# Interfaz_RS232.net
KiCad netlist of a schematic drawn in Altium Designer
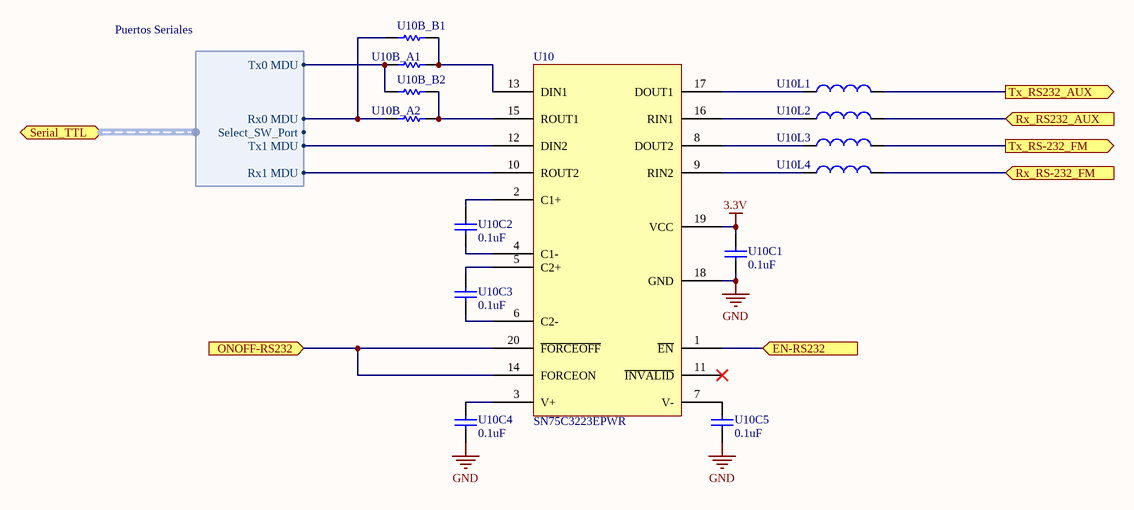
[diagram p0: Interfaz_RS232.SchDoc]

(export (version "E")
  (design (tool "Eeschema 10.0.6"))
  (components
    (comp (ref "U10")
      (value "SN75C3223EPWR")
      (footprint "TSSOP-20")
      (description "IC LINE DRVR/RCVR RS232 20-TSSOP")
      (fields (field (name "MANUFACTURER") "Texas Instruments"))
      (libsource (lib "LibreriaEstandar2") (part "SN75C3223EPWR"))
    )
    (comp (ref "U10B_A1")
      (value "~")
      (footprint "Bypass Bridge")
      (description "No Aplica")
      (libsource (lib "Miscellaneous Devices") (part "Res1"))
    )
    (comp (ref "U10B_A2")
      (value "~")
      (footprint "Bypass Bridge")
      (description "No Aplica")
      (libsource (lib "Miscellaneous Devices") (part "Res1"))
    )
    (comp (ref "U10B_B1")
      (value "~")
      (footprint "Bypass Bridge")
      (description "No Aplica")
      (libsource (lib "Miscellaneous Devices") (part "Res1"))
    )
    (comp (ref "U10B_B2")
      (value "~")
      (footprint "Bypass Bridge")
      (description "No Aplica")
      (libsource (lib "Miscellaneous Devices") (part "Res1"))
    )
    (comp (ref "U10C1")
      (value "0.1uF")
      (footprint "0603 - CAP")
      (description "CAP CERAMIC 0.1UF, 25V, X7R, 0603")
      (fields
        (field (name "MANUFACTURER PART NUMBER") "CGJ3E2X7R1E104K080AA")
        (field (name "MANUFACTURER") "TDK Corporation")
      )
      (libsource (lib "*") (part "Cap"))
    )
    (comp (ref "U10C2")
      (value "0.1uF")
      (footprint "0603 - CAP")
      (description "CAP CERAMIC 0.1UF, 25V, X7R, 0603")
      (fields
        (field (name "MANUFACTURER PART NUMBER") "CGJ3E2X7R1E104K080AA")
        (field (name "MANUFACTURER") "TDK Corporation")
      )
      (libsource (lib "*") (part "Cap"))
    )
    (comp (ref "U10C3")
      (value "0.1uF")
      (footprint "0603 - CAP")
      (description "CAP CERAMIC 0.1UF, 25V, X7R, 0603")
      (fields
        (field (name "MANUFACTURER PART NUMBER") "CGJ3E2X7R1E104K080AA")
        (field (name "MANUFACTURER") "TDK Corporation")
      )
      (libsource (lib "*") (part "Cap"))
    )
    (comp (ref "U10C4")
      (value "0.1uF")
      (footprint "0603 - CAP")
      (description "CAP CERAMIC 0.1UF, 25V, X7R, 0603")
      (fields
        (field (name "MANUFACTURER PART NUMBER") "CGJ3E2X7R1E104K080AA")
        (field (name "MANUFACTURER") "TDK Corporation")
      )
      (libsource (lib "*") (part "Cap"))
    )
    (comp (ref "U10C5")
      (value "0.1uF")
      (footprint "0603 - CAP")
      (description "CAP CERAMIC 0.1UF, 25V, X7R, 0603")
      (fields
        (field (name "MANUFACTURER PART NUMBER") "CGJ3E2X7R1E104K080AA")
        (field (name "MANUFACTURER") "TDK Corporation")
      )
      (libsource (lib "*") (part "Cap"))
    )
    (comp (ref "U10L1")
      (value "74279214")
      (footprint "1206-IND")
      (description "FERRITE BEAD 1000 OHM .20A 1206")
      (fields (field (name "MANUFACTURER") "Wurth Elektronik"))
      (libsource (lib "Miscellaneous Devices") (part "Inductor"))
    )
    (comp (ref "U10L2")
      (value "74279214")
      (footprint "1206-IND")
      (description "FERRITE BEAD 1000 OHM .20A 1206")
      (fields (field (name "MANUFACTURER") "Wurth Elektronik"))
      (libsource (lib "Miscellaneous Devices") (part "Inductor"))
    )
    (comp (ref "U10L3")
      (value "74279214")
      (footprint "1206-IND")
      (description "FERRITE BEAD 1000 OHM .20A 1206")
      (fields (field (name "MANUFACTURER") "Wurth Elektronik"))
      (libsource (lib "Miscellaneous Devices") (part "Inductor"))
    )
    (comp (ref "U10L4")
      (value "74279214")
      (footprint "1206-IND")
      (description "FERRITE BEAD 1000 OHM .20A 1206")
      (fields (field (name "MANUFACTURER") "Wurth Elektronik"))
      (libsource (lib "Miscellaneous Devices") (part "Inductor"))
    )
  )
  (nets
    (net (code "3") (name "/EN-RS232") (class "Default")
      (node (ref "U10") (pin "1") (pinfunction "~{EN}_1") (pintype "passive"))
    )
    (net (code "4") (name "/ONOFF-RS232") (class "Default")
      (node (ref "U10") (pin "14") (pinfunction "FORCEON_14") (pintype "passive"))
      (node (ref "U10") (pin "20") (pinfunction "~{FORCEOFF}_20") (pintype "passive"))
    )
    (net (code "5") (name "/Rx0 MDU") (class "Default")
      (node (ref "U10B_A2") (pin "1") (pinfunction "1_1") (pintype "passive"))
      (node (ref "U10B_B1") (pin "2") (pinfunction "2_2") (pintype "passive"))
    )
    (net (code "6") (name "/Rx1 MDU") (class "Default")
      (node (ref "U10") (pin "10") (pinfunction "ROUT2_10") (pintype "passive"))
    )
    (net (code "7") (name "/Rx_RS-232_FM") (class "Default")
      (node (ref "U10L4") (pin "2") (pinfunction "2_2") (pintype "passive"))
    )
    (net (code "8") (name "/Rx_RS232_AUX") (class "Default")
      (node (ref "U10L2") (pin "2") (pinfunction "2_2") (pintype "passive"))
    )
    (net (code "9") (name "/Tx0 MDU") (class "Default")
      (node (ref "U10B_A1") (pin "1") (pinfunction "1_1") (pintype "passive"))
      (node (ref "U10B_B2") (pin "2") (pinfunction "2_2") (pintype "passive"))
    )
    (net (code "10") (name "/Tx1 MDU") (class "Default")
      (node (ref "U10") (pin "12") (pinfunction "DIN2_12") (pintype "passive"))
    )
    (net (code "11") (name "/Tx_RS-232_FM") (class "Default")
      (node (ref "U10L3") (pin "2") (pinfunction "2_2") (pintype "passive"))
    )
    (net (code "12") (name "/Tx_RS232_AUX") (class "Default")
      (node (ref "U10L1") (pin "2") (pinfunction "2_2") (pintype "passive"))
    )
    (net (code "14") (name "3.3V") (class "Default")
      (node (ref "U10") (pin "19") (pinfunction "VCC_19") (pintype "passive"))
      (node (ref "U10C1") (pin "2") (pinfunction "2_2") (pintype "passive"))
    )
    (net (code "15") (name "GND") (class "Default")
      (node (ref "U10") (pin "18") (pinfunction "GND_18") (pintype "passive"))
      (node (ref "U10C1") (pin "1") (pinfunction "1_1") (pintype "passive"))
      (node (ref "U10C4") (pin "1") (pinfunction "1_1") (pintype "passive"))
      (node (ref "U10C5") (pin "1") (pinfunction "1_1") (pintype "passive"))
    )
    (net (code "16") (name "Net-(U10-C1+)") (class "Default")
      (node (ref "U10") (pin "2") (pinfunction "C1+_2") (pintype "passive"))
      (node (ref "U10C2") (pin "2") (pinfunction "2_2") (pintype "passive"))
    )
    (net (code "17") (name "Net-(U10-C1-)") (class "Default")
      (node (ref "U10") (pin "4") (pinfunction "C1-_4") (pintype "passive"))
      (node (ref "U10C2") (pin "1") (pinfunction "1_1") (pintype "passive"))
    )
    (net (code "18") (name "Net-(U10-C2+)") (class "Default")
      (node (ref "U10") (pin "5") (pinfunction "C2+_5") (pintype "passive"))
      (node (ref "U10C3") (pin "2") (pinfunction "2_2") (pintype "passive"))
    )
    (net (code "19") (name "Net-(U10-C2-)") (class "Default")
      (node (ref "U10") (pin "6") (pinfunction "C2-_6") (pintype "passive"))
      (node (ref "U10C3") (pin "1") (pinfunction "1_1") (pintype "passive"))
    )
    (net (code "20") (name "Net-(U10-DIN1)") (class "Default")
      (node (ref "U10") (pin "13") (pinfunction "DIN1_13") (pintype "passive"))
      (node (ref "U10B_A1") (pin "2") (pinfunction "2_2") (pintype "passive"))
      (node (ref "U10B_B1") (pin "1") (pinfunction "1_1") (pintype "passive"))
    )
    (net (code "21") (name "Net-(U10-DOUT1)") (class "Default")
      (node (ref "U10") (pin "17") (pinfunction "DOUT1_17") (pintype "passive"))
      (node (ref "U10L1") (pin "1") (pinfunction "1_1") (pintype "passive"))
    )
    (net (code "22") (name "Net-(U10-DOUT2)") (class "Default")
      (node (ref "U10") (pin "8") (pinfunction "DOUT2_8") (pintype "passive"))
      (node (ref "U10L3") (pin "1") (pinfunction "1_1") (pintype "passive"))
    )
    (net (code "23") (name "Net-(U10-RIN1)") (class "Default")
      (node (ref "U10") (pin "16") (pinfunction "RIN1_16") (pintype "passive"))
      (node (ref "U10L2") (pin "1") (pinfunction "1_1") (pintype "passive"))
    )
    (net (code "24") (name "Net-(U10-RIN2)") (class "Default")
      (node (ref "U10") (pin "9") (pinfunction "RIN2_9") (pintype "passive"))
      (node (ref "U10L4") (pin "1") (pinfunction "1_1") (pintype "passive"))
    )
    (net (code "25") (name "Net-(U10-ROUT1)") (class "Default")
      (node (ref "U10") (pin "15") (pinfunction "ROUT1_15") (pintype "passive"))
      (node (ref "U10B_A2") (pin "2") (pinfunction "2_2") (pintype "passive"))
      (node (ref "U10B_B2") (pin "1") (pinfunction "1_1") (pintype "passive"))
    )
    (net (code "26") (name "Net-(U10-V+)") (class "Default")
      (node (ref "U10") (pin "3") (pinfunction "V+_3") (pintype "passive"))
      (node (ref "U10C4") (pin "2") (pinfunction "2_2") (pintype "passive"))
    )
    (net (code "27") (name "Net-(U10-V-)") (class "Default")
      (node (ref "U10") (pin "7") (pinfunction "V-_7") (pintype "passive"))
      (node (ref "U10C5") (pin "2") (pinfunction "2_2") (pintype "passive"))
    )
    (net (code "28") (name "unconnected-(U10-~{INVALID}-Pad11)") (class "Default")
      (node (ref "U10") (pin "11") (pinfunction "~{INVALID}_11") (pintype "passive+no_connect"))
    )
  )
)
